# schematic.net
KiCad netlist of a schematic drawn in Altium Designer
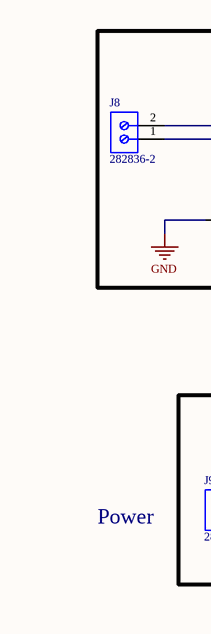
[diagram p0: schematic.SchDoc, left]
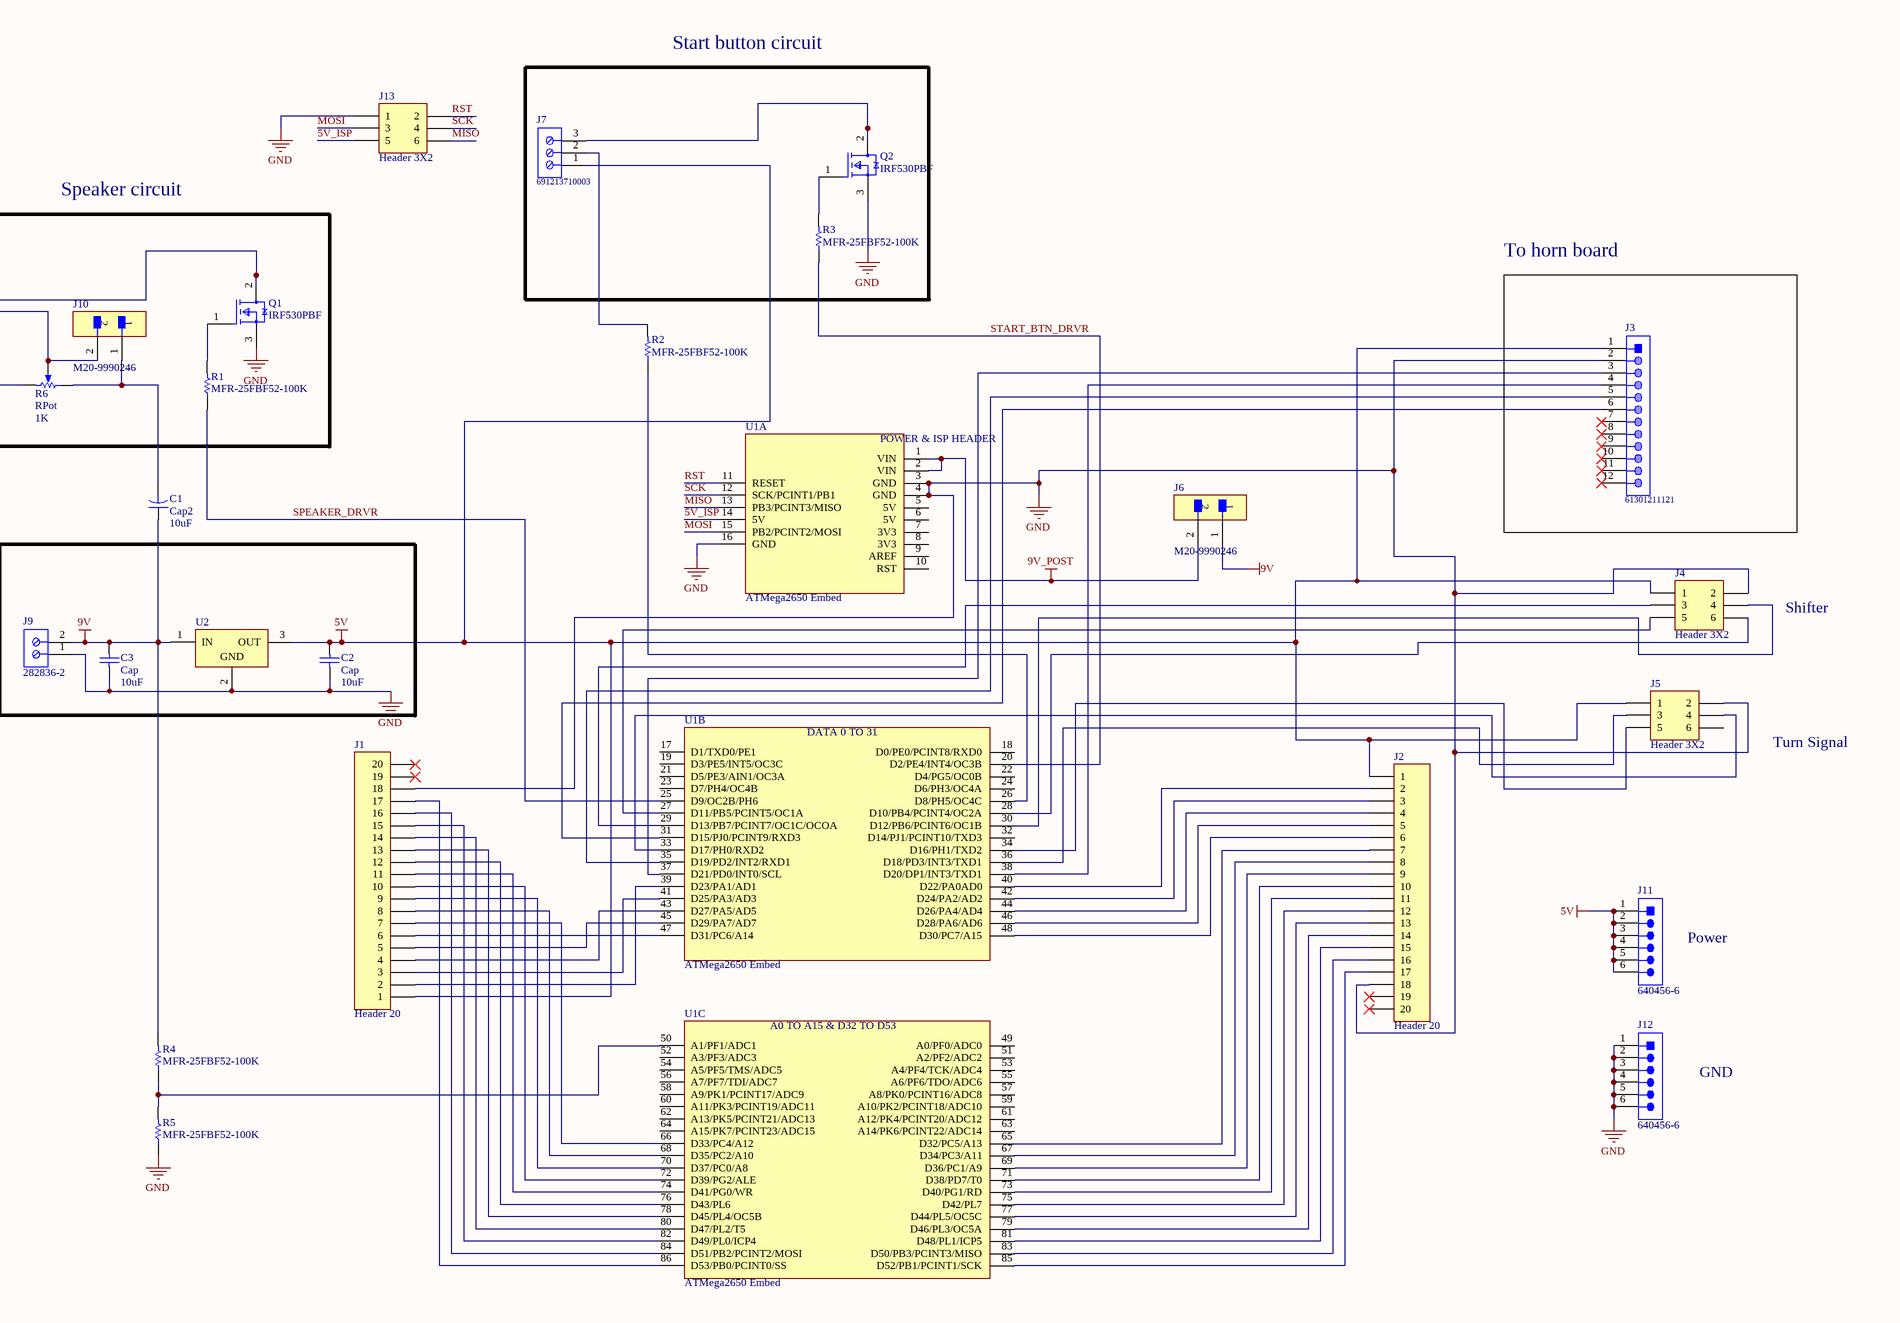
[diagram p1: schematic.SchDoc, right]

(export (version "E")
  (design (tool "Eeschema 10.0.6"))
  (components
    (comp (ref "C1")
      (value "Cap2")
      (footprint "CAPR5-4X5")
      (description "Capacitor")
      (fields (field (name "ALTIUM_VALUE") "10uF") (field (name "PUBLISHER") "Altium Limited"))
      (libsource (lib "Miscellaneous Devices") (part "Cap2"))
    )
    (comp (ref "C2")
      (value "Cap")
      (footprint "RAD-0.3")
      (description "Capacitor")
      (fields (field (name "ALTIUM_VALUE") "10uF") (field (name "PUBLISHER") "Altium Limited"))
      (libsource (lib "Miscellaneous Devices") (part "Cap"))
    )
    (comp (ref "C3")
      (value "Cap")
      (footprint "RAD-0.3")
      (description "Capacitor")
      (fields (field (name "ALTIUM_VALUE") "10uF") (field (name "PUBLISHER") "Altium Limited"))
      (libsource (lib "Miscellaneous Devices") (part "Cap"))
    )
    (comp (ref "J1")
      (value "Header 20")
      (footprint "HDR1X20")
      (description "Header, 20-Pin")
      (fields (field (name "PUBLISHER") "Altium Limited"))
      (libsource (lib "Miscellaneous Connectors") (part "Header 20"))
    )
    (comp (ref "J2")
      (value "Header 20")
      (footprint "HDR1X20")
      (description "Header, 20-Pin")
      (fields (field (name "PUBLISHER") "Altium Limited"))
      (libsource (lib "") (part "Header 20_1"))
    )
    (comp (ref "J3")
      (value "61301211121")
      (footprint "61301211121")
      (description "THT Vertical Pin Header WR-PHD, Pitch 2.54 mm, Single Row, 12 pins")
      (fields (field (name "MANUFACTURER") "Wurth Elektronik") (field (name "PUBLISHER") "WurthElektronik"))
      (libsource (lib "Altium Content Vault") (part "WE-CN-1P-M-R12"))
    )
    (comp (ref "J4")
      (value "Header 3X2")
      (footprint "HDR2X3")
      (description "Header, 3-Pin, Dual row")
      (fields (field (name "PUBLISHER") "Altium Limited"))
      (libsource (lib "Miscellaneous Connectors") (part "Header 3X2"))
    )
    (comp (ref "J5")
      (value "Header 3X2")
      (footprint "HDR2X3")
      (description "Header, 3-Pin, Dual row")
      (fields (field (name "PUBLISHER") "Altium Limited"))
      (libsource (lib "Miscellaneous Connectors") (part "Header 3X2"))
    )
    (comp (ref "J6")
      (value "M20-9990246")
      (footprint "FP-M20-9990246-MFG")
      (description "CONN HEADER VERT 2POS 2.54MM")
      (fields
        (field (name "OCTOPART") "https://octopart.com/m20-9990246-harwin-2590635")
        (field (name "MANUFACTURER") "Harwin")
      )
      (libsource (lib "Altium Content Vault") (part "3bc925449376181038e59eaffc5286c"))
    )
    (comp (ref "J7")
      (value "691213710003")
      (footprint "691213710003")
      (description "Serie 213 - 5.00 mm Horizontal Entry Modular with RisingCage Clamp WR-TBL, 3 pin")
      (fields (field (name "MANUFACTURER") "Wurth Elektronik") (field (name "PUBLISHER") "WurthElektronik"))
      (libsource (lib "Altium Content Vault") (part "WE-CN-1P-F-TB3"))
    )
    (comp (ref "J8")
      (value "282836-2")
      (footprint "TECO-282836-2_V")
      (description "Female Header, Pitch 5 mm, 1 x 2 Position, Height 10 mm, Tail Length 3.5 mm, Rohs, Bulk")
      (fields (field (name "VOLTAGE") "300V") (field (name "MANUFACTURER") "TE Connectivity"))
      (libsource (lib "Altium Content Vault") (part "CN-1P-F-TB2"))
    )
    (comp (ref "J9")
      (value "282836-2")
      (footprint "TECO-282836-2_V")
      (description "Female Header, Pitch 5 mm, 1 x 2 Position, Height 10 mm, Tail Length 3.5 mm, Rohs, Bulk")
      (fields (field (name "VOLTAGE") "300V") (field (name "MANUFACTURER") "TE Connectivity"))
      (libsource (lib "Altium Content Vault") (part "CN-1P-F-TB2"))
    )
    (comp (ref "J10")
      (value "M20-9990246")
      (footprint "FP-M20-9990246-MFG")
      (description "CONN HEADER VERT 2POS 2.54MM")
      (fields
        (field (name "OCTOPART") "https://octopart.com/m20-9990246-harwin-2590635")
        (field (name "MANUFACTURER") "Harwin")
      )
      (libsource (lib "Altium Content Vault") (part "3bc925449376181038e59eaffc5286c"))
    )
    (comp (ref "J11")
      (value "640456-6")
      (footprint "TECO-640456-6_V")
      (fields (field (name "MANUFACTURER") "TE Connectivity"))
      (libsource (lib "Altium Content Vault") (part "CN-1P-M-R6"))
    )
    (comp (ref "J12")
      (value "640456-6")
      (footprint "TECO-640456-6_V")
      (fields (field (name "MANUFACTURER") "TE Connectivity"))
      (libsource (lib "Altium Content Vault") (part "CN-1P-M-R6"))
    )
    (comp (ref "J13")
      (value "Header 3X2")
      (footprint "HDR2X3")
      (description "Header, 3-Pin, Dual row")
      (fields (field (name "PUBLISHER") "Altium Limited"))
      (libsource (lib "Miscellaneous Connectors") (part "Header 3X2"))
    )
    (comp (ref "Q1")
      (value "IRF530PBF")
      (footprint "FP-X15-0364-MFG")
      (description "MOSFET N-CH 100V 14A TO-220AB")
      (fields
        (field (name "MANUFACTURER") "Vishay")
        (field (name "OCTOPART") "https://octopart.com/irf530pbf-vishay-46547999")
      )
      (libsource (lib "Altium Content Vault") (part "277670f45256a45703965f138927d09"))
    )
    (comp (ref "Q2")
      (value "IRF530PBF")
      (footprint "FP-X15-0364-MFG")
      (description "MOSFET N-CH 100V 14A TO-220AB")
      (fields
        (field (name "MANUFACTURER") "Vishay")
        (field (name "OCTOPART") "https://octopart.com/irf530pbf-vishay-46547999")
      )
      (libsource (lib "Altium Content Vault") (part "277670f45256a45703965f138927d09"))
    )
    (comp (ref "R1")
      (value "MFR-25FBF52-100K")
      (footprint "RESA60-630X240")
      (description "Axial Resistor, 100 KOhm, +/- 1%, 0.25 W, -55 to 155 degC, 2-Pin THD, RoHS, Bulk")
      (fields (field (name "TOLERANCE") "1%"))
      (libsource (lib "Altium Content Vault") (part "RES-2"))
    )
    (comp (ref "R2")
      (value "MFR-25FBF52-100K")
      (footprint "RESA60-630X240")
      (description "Axial Resistor, 100 KOhm, +/- 1%, 0.25 W, -55 to 155 degC, 2-Pin THD, RoHS, Bulk")
      (fields (field (name "TOLERANCE") "1%"))
      (libsource (lib "Altium Content Vault") (part "RES-2"))
    )
    (comp (ref "R3")
      (value "MFR-25FBF52-100K")
      (footprint "RESA60-630X240")
      (description "Axial Resistor, 100 KOhm, +/- 1%, 0.25 W, -55 to 155 degC, 2-Pin THD, RoHS, Bulk")
      (fields (field (name "TOLERANCE") "1%"))
      (libsource (lib "Altium Content Vault") (part "RES-2"))
    )
    (comp (ref "R4")
      (value "MFR-25FBF52-100K")
      (footprint "RESA60-630X240")
      (description "Axial Resistor, 100 KOhm, +/- 1%, 0.25 W, -55 to 155 degC, 2-Pin THD, RoHS, Bulk")
      (fields (field (name "TOLERANCE") "1%"))
      (libsource (lib "Altium Content Vault") (part "RES-2"))
    )
    (comp (ref "R5")
      (value "MFR-25FBF52-100K")
      (footprint "RESA60-630X240")
      (description "Axial Resistor, 100 KOhm, +/- 1%, 0.25 W, -55 to 155 degC, 2-Pin THD, RoHS, Bulk")
      (fields (field (name "TOLERANCE") "1%"))
      (libsource (lib "Altium Content Vault") (part "RES-2"))
    )
    (comp (ref "R6")
      (value "RPot")
      (footprint "VR5")
      (description "Potentiometer")
      (fields (field (name "ALTIUM_VALUE") "1K") (field (name "PUBLISHER") "Altium Limited"))
      (libsource (lib "Miscellaneous Devices") (part "RPot"))
    )
    (comp (ref "U1")
      (value "ATMega2650 Embed")
      (footprint "ATMEGA2650 Embed")
      (libsource (lib "BopItLib") (part "ATMega2650 Embed"))
    )
    (comp (ref "U2")
      (value "L7812CV")
      (footprint "TO220")
      (description "Positive Voltage Regulator, 12V, 3-Pin TO-220")
      (libsource (lib "Altium Content Vault") (part "PM-REG-L4940-SIL3"))
    )
  )
  (nets
    (net (code "1") (name "/5V_ISP") (class "Default")
      (node (ref "J13") (pin "5") (pinfunction "5_5") (pintype "passive"))
      (node (ref "U1") (pin "14") (pinfunction "5V_14") (pintype "passive"))
    )
    (net (code "2") (name "/MISO") (class "Default")
      (node (ref "J13") (pin "6") (pinfunction "6_6") (pintype "passive"))
      (node (ref "U1") (pin "13") (pinfunction "PB3/PCINT3/MISO_13") (pintype "passive"))
    )
    (net (code "3") (name "/MOSI") (class "Default")
      (node (ref "J13") (pin "3") (pinfunction "3_3") (pintype "passive"))
      (node (ref "U1") (pin "15") (pinfunction "PB2/PCINT2/MOSI_15") (pintype "passive"))
    )
    (net (code "4") (name "/RST") (class "Default")
      (node (ref "J13") (pin "2") (pinfunction "2_2") (pintype "passive"))
      (node (ref "U1") (pin "11") (pinfunction "RESET_11") (pintype "passive"))
    )
    (net (code "5") (name "/SCK") (class "Default")
      (node (ref "J13") (pin "4") (pinfunction "4_4") (pintype "passive"))
      (node (ref "U1") (pin "12") (pinfunction "SCK/PCINT1/PB1_12") (pintype "passive"))
    )
    (net (code "6") (name "/SPEAKER_DRVR") (class "Default")
      (node (ref "R1") (pin "1") (pinfunction "1_1") (pintype "passive"))
      (node (ref "U1") (pin "25") (pinfunction "D9/OC2B/PH6_25") (pintype "passive"))
    )
    (net (code "7") (name "/START_BTN_DRVR") (class "Default")
      (node (ref "R3") (pin "1") (pinfunction "1_1") (pintype "passive"))
      (node (ref "U1") (pin "20") (pinfunction "D2/PE4/INT4/OC3B_20") (pintype "passive"))
    )
    (net (code "8") (name "5V") (class "Default")
      (node (ref "C2") (pin "2") (pinfunction "2_2") (pintype "passive"))
      (node (ref "J1") (pin "1") (pinfunction "1_1") (pintype "passive"))
      (node (ref "J11") (pin "1") (pinfunction "1_1") (pintype "passive"))
      (node (ref "J11") (pin "2") (pinfunction "2_2") (pintype "passive"))
      (node (ref "J11") (pin "3") (pinfunction "3_3") (pintype "passive"))
      (node (ref "J11") (pin "4") (pinfunction "4_4") (pintype "passive"))
      (node (ref "J11") (pin "5") (pinfunction "5_5") (pintype "passive"))
      (node (ref "J11") (pin "6") (pinfunction "6_6") (pintype "passive"))
      (node (ref "J2") (pin "1") (pinfunction "1_1") (pintype "passive"))
      (node (ref "J3") (pin "1") (pinfunction "1_1") (pintype "passive"))
      (node (ref "J4") (pin "1") (pinfunction "1_1") (pintype "passive"))
      (node (ref "J5") (pin "1") (pinfunction "1_1") (pintype "passive"))
      (node (ref "J7") (pin "1") (pinfunction "1_1") (pintype "passive"))
      (node (ref "U2") (pin "3") (pinfunction "OUT_3") (pintype "power_in"))
    )
    (net (code "9") (name "9V") (class "Default")
      (node (ref "C1") (pin "1") (pinfunction "1_1") (pintype "passive"))
      (node (ref "C3") (pin "2") (pinfunction "2_2") (pintype "passive"))
      (node (ref "J6") (pin "1") (pinfunction "1_1") (pintype "passive"))
      (node (ref "J9") (pin "2") (pinfunction "2_2") (pintype "passive"))
      (node (ref "R4") (pin "2") (pinfunction "2_2") (pintype "passive"))
      (node (ref "U2") (pin "1") (pinfunction "IN_1") (pintype "power_in"))
    )
    (net (code "10") (name "9V_POST") (class "Default")
      (node (ref "J6") (pin "2") (pinfunction "2_2") (pintype "passive"))
      (node (ref "U1") (pin "1") (pinfunction "VIN_1") (pintype "passive"))
      (node (ref "U1") (pin "2") (pinfunction "VIN_2") (pintype "passive"))
    )
    (net (code "11") (name "GND") (class "Default")
      (node (ref "C2") (pin "1") (pinfunction "1_1") (pintype "passive"))
      (node (ref "C3") (pin "1") (pinfunction "1_1") (pintype "passive"))
      (node (ref "J1") (pin "18") (pinfunction "18_18") (pintype "passive"))
      (node (ref "J12") (pin "1") (pinfunction "1_1") (pintype "passive"))
      (node (ref "J12") (pin "2") (pinfunction "2_2") (pintype "passive"))
      (node (ref "J12") (pin "3") (pinfunction "3_3") (pintype "passive"))
      (node (ref "J12") (pin "4") (pinfunction "4_4") (pintype "passive"))
      (node (ref "J12") (pin "5") (pinfunction "5_5") (pintype "passive"))
      (node (ref "J12") (pin "6") (pinfunction "6_6") (pintype "passive"))
      (node (ref "J13") (pin "1") (pinfunction "1_1") (pintype "passive"))
      (node (ref "J2") (pin "18") (pinfunction "18_18") (pintype "passive"))
      (node (ref "J3") (pin "2") (pinfunction "2_2") (pintype "passive"))
      (node (ref "J4") (pin "2") (pinfunction "2_2") (pintype "passive"))
      (node (ref "J5") (pin "2") (pinfunction "2_2") (pintype "passive"))
      (node (ref "J9") (pin "1") (pinfunction "1_1") (pintype "passive"))
      (node (ref "Q1") (pin "3") (pinfunction "S_3") (pintype "passive"))
      (node (ref "Q2") (pin "3") (pinfunction "S_3") (pintype "passive"))
      (node (ref "R5") (pin "1") (pinfunction "1_1") (pintype "passive"))
      (node (ref "R6") (pin "2") (pinfunction "BOT_2") (pintype "passive"))
      (node (ref "U1") (pin "16") (pinfunction "GND_16") (pintype "passive"))
      (node (ref "U1") (pin "3") (pinfunction "GND_3") (pintype "passive"))
      (node (ref "U1") (pin "4") (pinfunction "GND_4") (pintype "passive"))
      (node (ref "U2") (pin "2") (pinfunction "GND_2") (pintype "power_in"))
    )
    (net (code "12") (name "Net-(J7-Pad2)") (class "Default")
      (node (ref "J7") (pin "2") (pinfunction "2_2") (pintype "passive"))
      (node (ref "R2") (pin "2") (pinfunction "2_2") (pintype "passive"))
    )
    (net (code "13") (name "Net-(Q1-D)") (class "Default")
      (node (ref "J8") (pin "2") (pinfunction "2_2") (pintype "passive"))
      (node (ref "Q1") (pin "2") (pinfunction "D_2") (pintype "passive"))
    )
    (net (code "14") (name "Net-(Q1-G)") (class "Default")
      (node (ref "Q1") (pin "1") (pinfunction "G_1") (pintype "passive"))
      (node (ref "R1") (pin "2") (pinfunction "2_2") (pintype "passive"))
    )
    (net (code "15") (name "Net-(Q2-D)") (class "Default")
      (node (ref "J7") (pin "3") (pinfunction "3_3") (pintype "passive"))
      (node (ref "Q2") (pin "2") (pinfunction "D_2") (pintype "passive"))
    )
    (net (code "16") (name "Net-(Q2-G)") (class "Default")
      (node (ref "Q2") (pin "1") (pinfunction "G_1") (pintype "passive"))
      (node (ref "R3") (pin "2") (pinfunction "2_2") (pintype "passive"))
    )
    (net (code "17") (name "Net-(R6-TAP)") (class "Default")
      (node (ref "J10") (pin "2") (pinfunction "2_2") (pintype "passive"))
      (node (ref "J8") (pin "1") (pinfunction "1_1") (pintype "passive"))
      (node (ref "R6") (pin "3") (pinfunction "TAP_3") (pintype "passive"))
    )
    (net (code "18") (name "Net-(R6-TOP)") (class "Default")
      (node (ref "C1") (pin "2") (pinfunction "2_2") (pintype "passive"))
      (node (ref "J10") (pin "1") (pinfunction "1_1") (pintype "passive"))
      (node (ref "R6") (pin "1") (pinfunction "TOP_1") (pintype "passive"))
    )
    (net (code "19") (name "Net-(U1B-D8{slash}PH5{slash}OC4C)") (class "Default")
      (node (ref "R2") (pin "1") (pinfunction "1_1") (pintype "passive"))
      (node (ref "U1") (pin "26") (pinfunction "D8/PH5/OC4C_26") (pintype "passive"))
    )
    (net (code "20") (name "Net-(U1B-D10{slash}PB4{slash}PCINT4{slash}OC2A)") (class "Default")
      (node (ref "J4") (pin "6") (pinfunction "6_6") (pintype "passive"))
      (node (ref "U1") (pin "28") (pinfunction "D10/PB4/PCINT4/OC2A_28") (pintype "passive"))
    )
    (net (code "21") (name "Net-(U1B-D11{slash}PB5{slash}PCINT5{slash}OC1A)") (class "Default")
      (node (ref "J4") (pin "5") (pinfunction "5_5") (pintype "passive"))
      (node (ref "U1") (pin "27") (pinfunction "D11/PB5/PCINT5/OC1A_27") (pintype "passive"))
    )
    (net (code "22") (name "Net-(U1B-D12{slash}PB6{slash}PCINT6{slash}OC1B)") (class "Default")
      (node (ref "J4") (pin "4") (pinfunction "4_4") (pintype "passive"))
      (node (ref "U1") (pin "30") (pinfunction "D12/PB6/PCINT6/OC1B_30") (pintype "passive"))
    )
    (net (code "23") (name "Net-(U1B-D13{slash}PB7{slash}PCINT7{slash}OC1C{slash}OCOA)") (class "Default")
      (node (ref "J4") (pin "3") (pinfunction "3_3") (pintype "passive"))
      (node (ref "U1") (pin "29") (pinfunction "D13/PB7/PCINT7/OC1C/OCOA_29") (pintype "passive"))
    )
    (net (code "24") (name "Net-(U1B-D15{slash}PJ0{slash}PCINT9{slash}RXD3)") (class "Default")
      (node (ref "J3") (pin "6") (pinfunction "6_6") (pintype "passive"))
      (node (ref "U1") (pin "31") (pinfunction "D15/PJ0/PCINT9/RXD3_31") (pintype "passive"))
    )
    (net (code "25") (name "Net-(U1B-D16{slash}PH1{slash}TXD2)") (class "Default")
      (node (ref "J5") (pin "5") (pinfunction "5_5") (pintype "passive"))
      (node (ref "U1") (pin "34") (pinfunction "D16/PH1/TXD2_34") (pintype "passive"))
    )
    (net (code "26") (name "Net-(U1B-D17{slash}PH0{slash}RXD2)") (class "Default")
      (node (ref "J5") (pin "4") (pinfunction "4_4") (pintype "passive"))
      (node (ref "U1") (pin "33") (pinfunction "D17/PH0/RXD2_33") (pintype "passive"))
    )
    (net (code "27") (name "Net-(U1B-D18{slash}PD3{slash}INT3{slash}TXD1)") (class "Default")
      (node (ref "J5") (pin "3") (pinfunction "3_3") (pintype "passive"))
      (node (ref "U1") (pin "36") (pinfunction "D18/PD3/INT3/TXD1_36") (pintype "passive"))
    )
    (net (code "28") (name "Net-(U1B-D19{slash}PD2{slash}INT2{slash}RXD1)") (class "Default")
      (node (ref "J3") (pin "5") (pinfunction "5_5") (pintype "passive"))
      (node (ref "U1") (pin "35") (pinfunction "D19/PD2/INT2/RXD1_35") (pintype "passive"))
    )
    (net (code "29") (name "Net-(U1B-D20{slash}DP1{slash}INT3{slash}TXD1)") (class "Default")
      (node (ref "J3") (pin "4") (pinfunction "4_4") (pintype "passive"))
      (node (ref "U1") (pin "38") (pinfunction "D20/DP1/INT3/TXD1_38") (pintype "passive"))
    )
    (net (code "30") (name "Net-(U1B-D21{slash}PD0{slash}INT0{slash}SCL)") (class "Default")
      (node (ref "J3") (pin "3") (pinfunction "3_3") (pintype "passive"))
      (node (ref "U1") (pin "37") (pinfunction "D21/PD0/INT0/SCL_37") (pintype "passive"))
    )
    (net (code "31") (name "Net-(U1B-D22{slash}PA0AD0)") (class "Default")
      (node (ref "J2") (pin "2") (pinfunction "2_2") (pintype "passive"))
      (node (ref "U1") (pin "40") (pinfunction "D22/PA0AD0_40") (pintype "passive"))
    )
    (net (code "32") (name "Net-(U1B-D23{slash}PA1{slash}AD1)") (class "Default")
      (node (ref "J1") (pin "2") (pinfunction "2_2") (pintype "passive"))
      (node (ref "U1") (pin "39") (pinfunction "D23/PA1/AD1_39") (pintype "passive"))
    )
    (net (code "33") (name "Net-(U1B-D24{slash}PA2{slash}AD2)") (class "Default")
      (node (ref "J2") (pin "3") (pinfunction "3_3") (pintype "passive"))
      (node (ref "U1") (pin "42") (pinfunction "D24/PA2/AD2_42") (pintype "passive"))
    )
    (net (code "34") (name "Net-(U1B-D25{slash}PA3{slash}AD3)") (class "Default")
      (node (ref "J1") (pin "3") (pinfunction "3_3") (pintype "passive"))
      (node (ref "U1") (pin "41") (pinfunction "D25/PA3/AD3_41") (pintype "passive"))
    )
    (net (code "35") (name "Net-(U1B-D26{slash}PA4{slash}AD4)") (class "Default")
      (node (ref "J2") (pin "4") (pinfunction "4_4") (pintype "passive"))
      (node (ref "U1") (pin "44") (pinfunction "D26/PA4/AD4_44") (pintype "passive"))
    )
    (net (code "36") (name "Net-(U1B-D27{slash}PA5{slash}AD5)") (class "Default")
      (node (ref "J1") (pin "4") (pinfunction "4_4") (pintype "passive"))
      (node (ref "U1") (pin "43") (pinfunction "D27/PA5/AD5_43") (pintype "passive"))
    )
    (net (code "37") (name "Net-(U1B-D28{slash}PA6{slash}AD6)") (class "Default")
      (node (ref "J2") (pin "5") (pinfunction "5_5") (pintype "passive"))
      (node (ref "U1") (pin "46") (pinfunction "D28/PA6/AD6_46") (pintype "passive"))
    )
    (net (code "38") (name "Net-(U1B-D29{slash}PA7{slash}AD7)") (class "Default")
      (node (ref "J1") (pin "5") (pinfunction "5_5") (pintype "passive"))
      (node (ref "U1") (pin "45") (pinfunction "D29/PA7/AD7_45") (pintype "passive"))
    )
    (net (code "39") (name "Net-(U1B-D30{slash}PC7{slash}A15)") (class "Default")
      (node (ref "J2") (pin "6") (pinfunction "6_6") (pintype "passive"))
      (node (ref "U1") (pin "48") (pinfunction "D30/PC7/A15_48") (pintype "passive"))
    )
    (net (code "40") (name "Net-(U1B-D31{slash}PC6{slash}A14)") (class "Default")
      (node (ref "J1") (pin "6") (pinfunction "6_6") (pintype "passive"))
      (node (ref "U1") (pin "47") (pinfunction "D31/PC6/A14_47") (pintype "passive"))
    )
    (net (code "41") (name "Net-(U1C-A1{slash}PF1{slash}ADC1)") (class "Default")
      (node (ref "R4") (pin "1") (pinfunction "1_1") (pintype "passive"))
      (node (ref "R5") (pin "2") (pinfunction "2_2") (pintype "passive"))
      (node (ref "U1") (pin "50") (pinfunction "A1/PF1/ADC1_50") (pintype "passive"))
    )
    (net (code "42") (name "Net-(U1C-D32{slash}PC5{slash}A13)") (class "Default")
      (node (ref "J2") (pin "7") (pinfunction "7_7") (pintype "passive"))
      (node (ref "U1") (pin "65") (pinfunction "D32/PC5/A13_65") (pintype "passive"))
    )
    (net (code "43") (name "Net-(U1C-D33{slash}PC4{slash}A12)") (class "Default")
      (node (ref "J1") (pin "7") (pinfunction "7_7") (pintype "passive"))
      (node (ref "U1") (pin "66") (pinfunction "D33/PC4/A12_66") (pintype "passive"))
    )
    (net (code "44") (name "Net-(U1C-D34{slash}PC3{slash}A11)") (class "Default")
      (node (ref "J2") (pin "8") (pinfunction "8_8") (pintype "passive"))
      (node (ref "U1") (pin "67") (pinfunction "D34/PC3/A11_67") (pintype "passive"))
    )
    (net (code "45") (name "Net-(U1C-D35{slash}PC2{slash}A10)") (class "Default")
      (node (ref "J1") (pin "8") (pinfunction "8_8") (pintype "passive"))
      (node (ref "U1") (pin "68") (pinfunction "D35/PC2/A10_68") (pintype "passive"))
    )
    (net (code "46") (name "Net-(U1C-D36{slash}PC1{slash}A9)") (class "Default")
      (node (ref "J2") (pin "9") (pinfunction "9_9") (pintype "passive"))
      (node (ref "U1") (pin "69") (pinfunction "D36/PC1/A9_69") (pintype "passive"))
    )
    (net (code "47") (name "Net-(U1C-D37{slash}PC0{slash}A8)") (class "Default")
      (node (ref "J1") (pin "9") (pinfunction "9_9") (pintype "passive"))
      (node (ref "U1") (pin "70") (pinfunction "D37/PC0/A8_70") (pintype "passive"))
    )
    (net (code "48") (name "Net-(U1C-D38{slash}PD7{slash}T0)") (class "Default")
      (node (ref "J2") (pin "10") (pinfunction "10_10") (pintype "passive"))
      (node (ref "U1") (pin "71") (pinfunction "D38/PD7/T0_71") (pintype "passive"))
    )
    (net (code "49") (name "Net-(U1C-D39{slash}PG2{slash}ALE)") (class "Default")
      (node (ref "J1") (pin "10") (pinfunction "10_10") (pintype "passive"))
      (node (ref "U1") (pin "72") (pinfunction "D39/PG2/ALE_72") (pintype "passive"))
    )
    (net (code "50") (name "Net-(U1C-D40{slash}PG1{slash}RD)") (class "Default")
      (node (ref "J2") (pin "11") (pinfunction "11_11") (pintype "passive"))
      (node (ref "U1") (pin "73") (pinfunction "D40/PG1/RD_73") (pintype "passive"))
    )
    (net (code "51") (name "Net-(U1C-D41{slash}PG0{slash}WR)") (class "Default")
      (node (ref "J1") (pin "11") (pinfunction "11_11") (pintype "passive"))
      (node (ref "U1") (pin "74") (pinfunction "D41/PG0/WR_74") (pintype "passive"))
    )
    (net (code "52") (name "Net-(U1C-D42{slash}PL7)") (class "Default")
      (node (ref "J2") (pin "12") (pinfunction "12_12") (pintype "passive"))
      (node (ref "U1") (pin "75") (pinfunction "D42/PL7_75") (pintype "passive"))
    )
    (net (code "53") (name "Net-(U1C-D43{slash}PL6)") (class "Default")
      (node (ref "J1") (pin "12") (pinfunction "12_12") (pintype "passive"))
      (node (ref "U1") (pin "76") (pinfunction "D43/PL6_76") (pintype "passive"))
    )
    (net (code "54") (name "Net-(U1C-D44{slash}PL5{slash}OC5C)") (class "Default")
      (node (ref "J2") (pin "13") (pinfunction "13_13") (pintype "passive"))
      (node (ref "U1") (pin "77") (pinfunction "D44/PL5/OC5C_77") (pintype "passive"))
    )
    (net (code "55") (name "Net-(U1C-D45{slash}PL4{slash}OC5B)") (class "Default")
      (node (ref "J1") (pin "13") (pinfunction "13_13") (pintype "passive"))
      (node (ref "U1") (pin "78") (pinfunction "D45/PL4/OC5B_78") (pintype "passive"))
    )
    (net (code "56") (name "Net-(U1C-D46{slash}PL3{slash}OC5A)") (class "Default")
      (node (ref "J2") (pin "14") (pinfunction "14_14") (pintype "passive"))
      (node (ref "U1") (pin "79") (pinfunction "D46/PL3/OC5A_79") (pintype "passive"))
    )
    (net (code "57") (name "Net-(U1C-D47{slash}PL2{slash}T5)") (class "Default")
      (node (ref "J1") (pin "14") (pinfunction "14_14") (pintype "passive"))
      (node (ref "U1") (pin "80") (pinfunction "D47/PL2/T5_80") (pintype "passive"))
    )
    (net (code "58") (name "Net-(U1C-D48{slash}PL1{slash}ICP5)") (class "Default")
      (node (ref "J2") (pin "15") (pinfunction "15_15") (pintype "passive"))
      (node (ref "U1") (pin "81") (pinfunction "D48/PL1/ICP5_81") (pintype "passive"))
    )
    (net (code "59") (name "Net-(U1C-D49{slash}PL0{slash}ICP4)") (class "Default")
      (node (ref "J1") (pin "15") (pinfunction "15_15") (pintype "passive"))
      (node (ref "U1") (pin "82") (pinfunction "D49/PL0/ICP4_82") (pintype "passive"))
    )
    (net (code "60") (name "Net-(U1C-D50{slash}PB3{slash}PCINT3{slash}MISO)") (class "Default")
      (node (ref "J2") (pin "16") (pinfunction "16_16") (pintype "passive"))
      (node (ref "U1") (pin "83") (pinfunction "D50/PB3/PCINT3/MISO_83") (pintype "passive"))
    )
    (net (code "61") (name "Net-(U1C-D51{slash}PB2{slash}PCINT2{slash}MOSI)") (class "Default")
      (node (ref "J1") (pin "16") (pinfunction "16_16") (pintype "passive"))
      (node (ref "U1") (pin "84") (pinfunction "D51/PB2/PCINT2/MOSI_84") (pintype "passive"))
    )
    (net (code "62") (name "Net-(U1C-D52{slash}PB1{slash}PCINT1{slash}SCK)") (class "Default")
      (node (ref "J2") (pin "17") (pinfunction "17_17") (pintype "passive"))
      (node (ref "U1") (pin "85") (pinfunction "D52/PB1/PCINT1/SCK_85") (pintype "passive"))
    )
    (net (code "63") (name "Net-(U1C-D53{slash}PB0{slash}PCINT0{slash}SS)") (class "Default")
      (node (ref "J1") (pin "17") (pinfunction "17_17") (pintype "passive"))
      (node (ref "U1") (pin "86") (pinfunction "D53/PB0/PCINT0/SS_86") (pintype "passive"))
    )
    (net (code "64") (name "unconnected-(J1-Pad19)") (class "Default")
      (node (ref "J1") (pin "19") (pinfunction "19_19") (pintype "passive+no_connect"))
    )
    (net (code "65") (name "unconnected-(J1-Pad20)") (class "Default")
      (node (ref "J1") (pin "20") (pinfunction "20_20") (pintype "passive+no_connect"))
    )
    (net (code "66") (name "unconnected-(J2-Pad19)") (class "Default")
      (node (ref "J2") (pin "19") (pinfunction "19_19") (pintype "passive+no_connect"))
    )
    (net (code "67") (name "unconnected-(J2-Pad20)") (class "Default")
      (node (ref "J2") (pin "20") (pinfunction "20_20") (pintype "passive+no_connect"))
    )
    (net (code "68") (name "unconnected-(J3-Pad7)") (class "Default")
      (node (ref "J3") (pin "7") (pinfunction "7_7") (pintype "passive+no_connect"))
    )
    (net (code "69") (name "unconnected-(J3-Pad8)") (class "Default")
      (node (ref "J3") (pin "8") (pinfunction "8_8") (pintype "passive+no_connect"))
    )
    (net (code "70") (name "unconnected-(J3-Pad9)") (class "Default")
      (node (ref "J3") (pin "9") (pinfunction "9_9") (pintype "passive+no_connect"))
    )
    (net (code "71") (name "unconnected-(J3-Pad10)") (class "Default")
      (node (ref "J3") (pin "10") (pinfunction "10_10") (pintype "passive+no_connect"))
    )
    (net (code "72") (name "unconnected-(J3-Pad11)") (class "Default")
      (node (ref "J3") (pin "11") (pinfunction "11_11") (pintype "passive+no_connect"))
    )
    (net (code "73") (name "unconnected-(J3-Pad12)") (class "Default")
      (node (ref "J3") (pin "12") (pinfunction "12_12") (pintype "passive+no_connect"))
    )
    (net (code "74") (name "unconnected-(J5-Pad6)") (class "Default")
      (node (ref "J5") (pin "6") (pinfunction "6_6") (pintype "passive"))
    )
    (net (code "75") (name "unconnected-(U1A-3V3-Pad7)") (class "Default")
      (node (ref "U1") (pin "7") (pinfunction "3V3_7") (pintype "passive"))
    )
    (net (code "76") (name "unconnected-(U1A-3V3-Pad8)") (class "Default")
      (node (ref "U1") (pin "8") (pinfunction "3V3_8") (pintype "passive"))
    )
    (net (code "77") (name "unconnected-(U1A-5V-Pad5)") (class "Default")
      (node (ref "U1") (pin "5") (pinfunction "5V_5") (pintype "passive"))
    )
    (net (code "78") (name "unconnected-(U1A-5V-Pad6)") (class "Default")
      (node (ref "U1") (pin "6") (pinfunction "5V_6") (pintype "passive"))
    )
    (net (code "79") (name "unconnected-(U1A-AREF-Pad9)") (class "Default")
      (node (ref "U1") (pin "9") (pinfunction "AREF_9") (pintype "passive"))
    )
    (net (code "80") (name "unconnected-(U1A-RST-Pad10)") (class "Default")
      (node (ref "U1") (pin "10") (pinfunction "RST_10") (pintype "passive"))
    )
    (net (code "81") (name "unconnected-(U1B-D0{slash}PE0{slash}PCINT8{slash}RXD0-Pad18)") (class "Default")
      (node (ref "U1") (pin "18") (pinfunction "D0/PE0/PCINT8/RXD0_18") (pintype "passive"))
    )
    (net (code "82") (name "unconnected-(U1B-D1{slash}TXD0{slash}PE1-Pad17)") (class "Default")
      (node (ref "U1") (pin "17") (pinfunction "D1/TXD0/PE1_17") (pintype "passive"))
    )
    (net (code "83") (name "unconnected-(U1B-D3{slash}PE5{slash}INT5{slash}OC3C-Pad19)") (class "Default")
      (node (ref "U1") (pin "19") (pinfunction "D3/PE5/INT5/OC3C_19") (pintype "passive"))
    )
    (net (code "84") (name "unconnected-(U1B-D4{slash}PG5{slash}OC0B-Pad22)") (class "Default")
      (node (ref "U1") (pin "22") (pinfunction "D4/PG5/OC0B_22") (pintype "passive"))
    )
    (net (code "85") (name "unconnected-(U1B-D5{slash}PE3{slash}AIN1{slash}OC3A-Pad21)") (class "Default")
      (node (ref "U1") (pin "21") (pinfunction "D5/PE3/AIN1/OC3A_21") (pintype "passive"))
    )
    (net (code "86") (name "unconnected-(U1B-D6{slash}PH3{slash}OC4A-Pad24)") (class "Default")
      (node (ref "U1") (pin "24") (pinfunction "D6/PH3/OC4A_24") (pintype "passive"))
    )
    (net (code "87") (name "unconnected-(U1B-D7{slash}PH4{slash}OC4B-Pad23)") (class "Default")
      (node (ref "U1") (pin "23") (pinfunction "D7/PH4/OC4B_23") (pintype "passive"))
    )
    (net (code "88") (name "unconnected-(U1B-D14{slash}PJ1{slash}PCINT10{slash}TXD3-Pad32)") (class "Default")
      (node (ref "U1") (pin "32") (pinfunction "D14/PJ1/PCINT10/TXD3_32") (pintype "passive"))
    )
    (net (code "89") (name "unconnected-(U1C-A0{slash}PF0{slash}ADC0-Pad49)") (class "Default")
      (node (ref "U1") (pin "49") (pinfunction "A0/PF0/ADC0_49") (pintype "passive"))
    )
    (net (code "90") (name "unconnected-(U1C-A2{slash}PF2{slash}ADC2-Pad51)") (class "Default")
      (node (ref "U1") (pin "51") (pinfunction "A2/PF2/ADC2_51") (pintype "passive"))
    )
    (net (code "91") (name "unconnected-(U1C-A3{slash}PF3{slash}ADC3-Pad52)") (class "Default")
      (node (ref "U1") (pin "52") (pinfunction "A3/PF3/ADC3_52") (pintype "passive"))
    )
    (net (code "92") (name "unconnected-(U1C-A4{slash}PF4{slash}TCK{slash}ADC4-Pad53)") (class "Default")
      (node (ref "U1") (pin "53") (pinfunction "A4/PF4/TCK/ADC4_53") (pintype "passive"))
    )
    (net (code "93") (name "unconnected-(U1C-A5{slash}PF5{slash}TMS{slash}ADC5-Pad54)") (class "Default")
      (node (ref "U1") (pin "54") (pinfunction "A5/PF5/TMS/ADC5_54") (pintype "passive"))
    )
    (net (code "94") (name "unconnected-(U1C-A6{slash}PF6{slash}TDO{slash}ADC6-Pad55)") (class "Default")
      (node (ref "U1") (pin "55") (pinfunction "A6/PF6/TDO/ADC6_55") (pintype "passive"))
    )
    (net (code "95") (name "unconnected-(U1C-A7{slash}PF7{slash}TDI{slash}ADC7-Pad56)") (class "Default")
      (node (ref "U1") (pin "56") (pinfunction "A7/PF7/TDI/ADC7_56") (pintype "passive"))
    )
    (net (code "96") (name "unconnected-(U1C-A8{slash}PK0{slash}PCINT16{slash}ADC8-Pad57)") (class "Default")
      (node (ref "U1") (pin "57") (pinfunction "A8/PK0/PCINT16/ADC8_57") (pintype "passive"))
    )
    (net (code "97") (name "unconnected-(U1C-A9{slash}PK1{slash}PCINT17{slash}ADC9-Pad58)") (class "Default")
      (node (ref "U1") (pin "58") (pinfunction "A9/PK1/PCINT17/ADC9_58") (pintype "passive"))
    )
    (net (code "98") (name "unconnected-(U1C-A10{slash}PK2{slash}PCINT18{slash}ADC10-Pad59)") (class "Default")
      (node (ref "U1") (pin "59") (pinfunction "A10/PK2/PCINT18/ADC10_59") (pintype "passive"))
    )
    (net (code "99") (name "unconnected-(U1C-A11{slash}PK3{slash}PCINT19{slash}ADC11-Pad60)") (class "Default")
      (node (ref "U1") (pin "60") (pinfunction "A11/PK3/PCINT19/ADC11_60") (pintype "passive"))
    )
    (net (code "100") (name "unconnected-(U1C-A12{slash}PK4{slash}PCINT20{slash}ADC12-Pad61)") (class "Default")
      (node (ref "U1") (pin "61") (pinfunction "A12/PK4/PCINT20/ADC12_61") (pintype "passive"))
    )
    (net (code "101") (name "unconnected-(U1C-A13{slash}PK5{slash}PCINT21{slash}ADC13-Pad62)") (class "Default")
      (node (ref "U1") (pin "62") (pinfunction "A13/PK5/PCINT21/ADC13_62") (pintype "passive"))
    )
    (net (code "102") (name "unconnected-(U1C-A14{slash}PK6{slash}PCINT22{slash}ADC14-Pad63)") (class "Default")
      (node (ref "U1") (pin "63") (pinfunction "A14/PK6/PCINT22/ADC14_63") (pintype "passive"))
    )
    (net (code "103") (name "unconnected-(U1C-A15{slash}PK7{slash}PCINT23{slash}ADC15-Pad64)") (class "Default")
      (node (ref "U1") (pin "64") (pinfunction "A15/PK7/PCINT23/ADC15_64") (pintype "passive"))
    )
  )
)
